# Tray2_BCR.net
KiCad netlist of a schematic drawn in Altium Designer
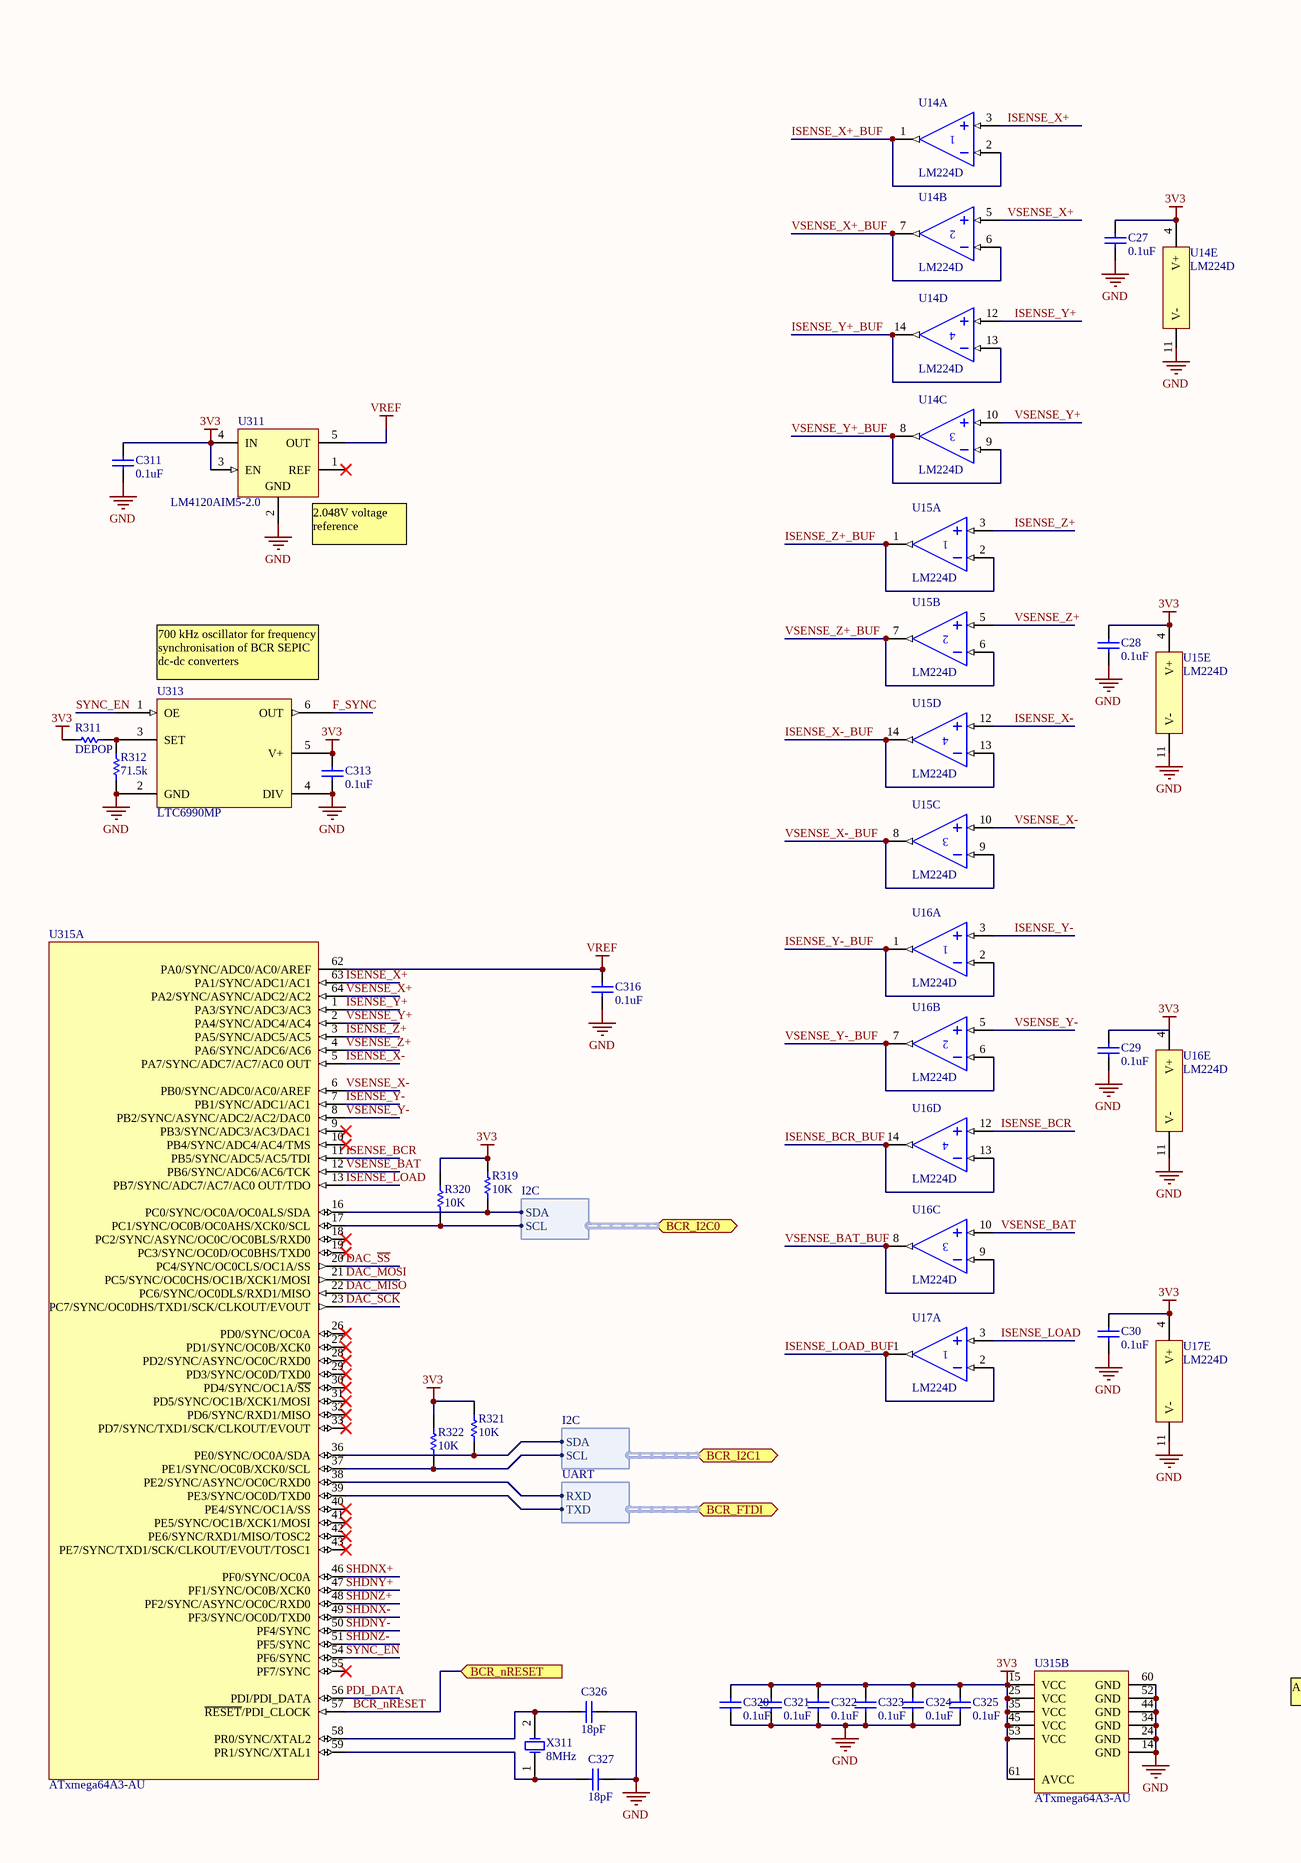
[diagram p0: Tray2_BCR.SchDoc, left]
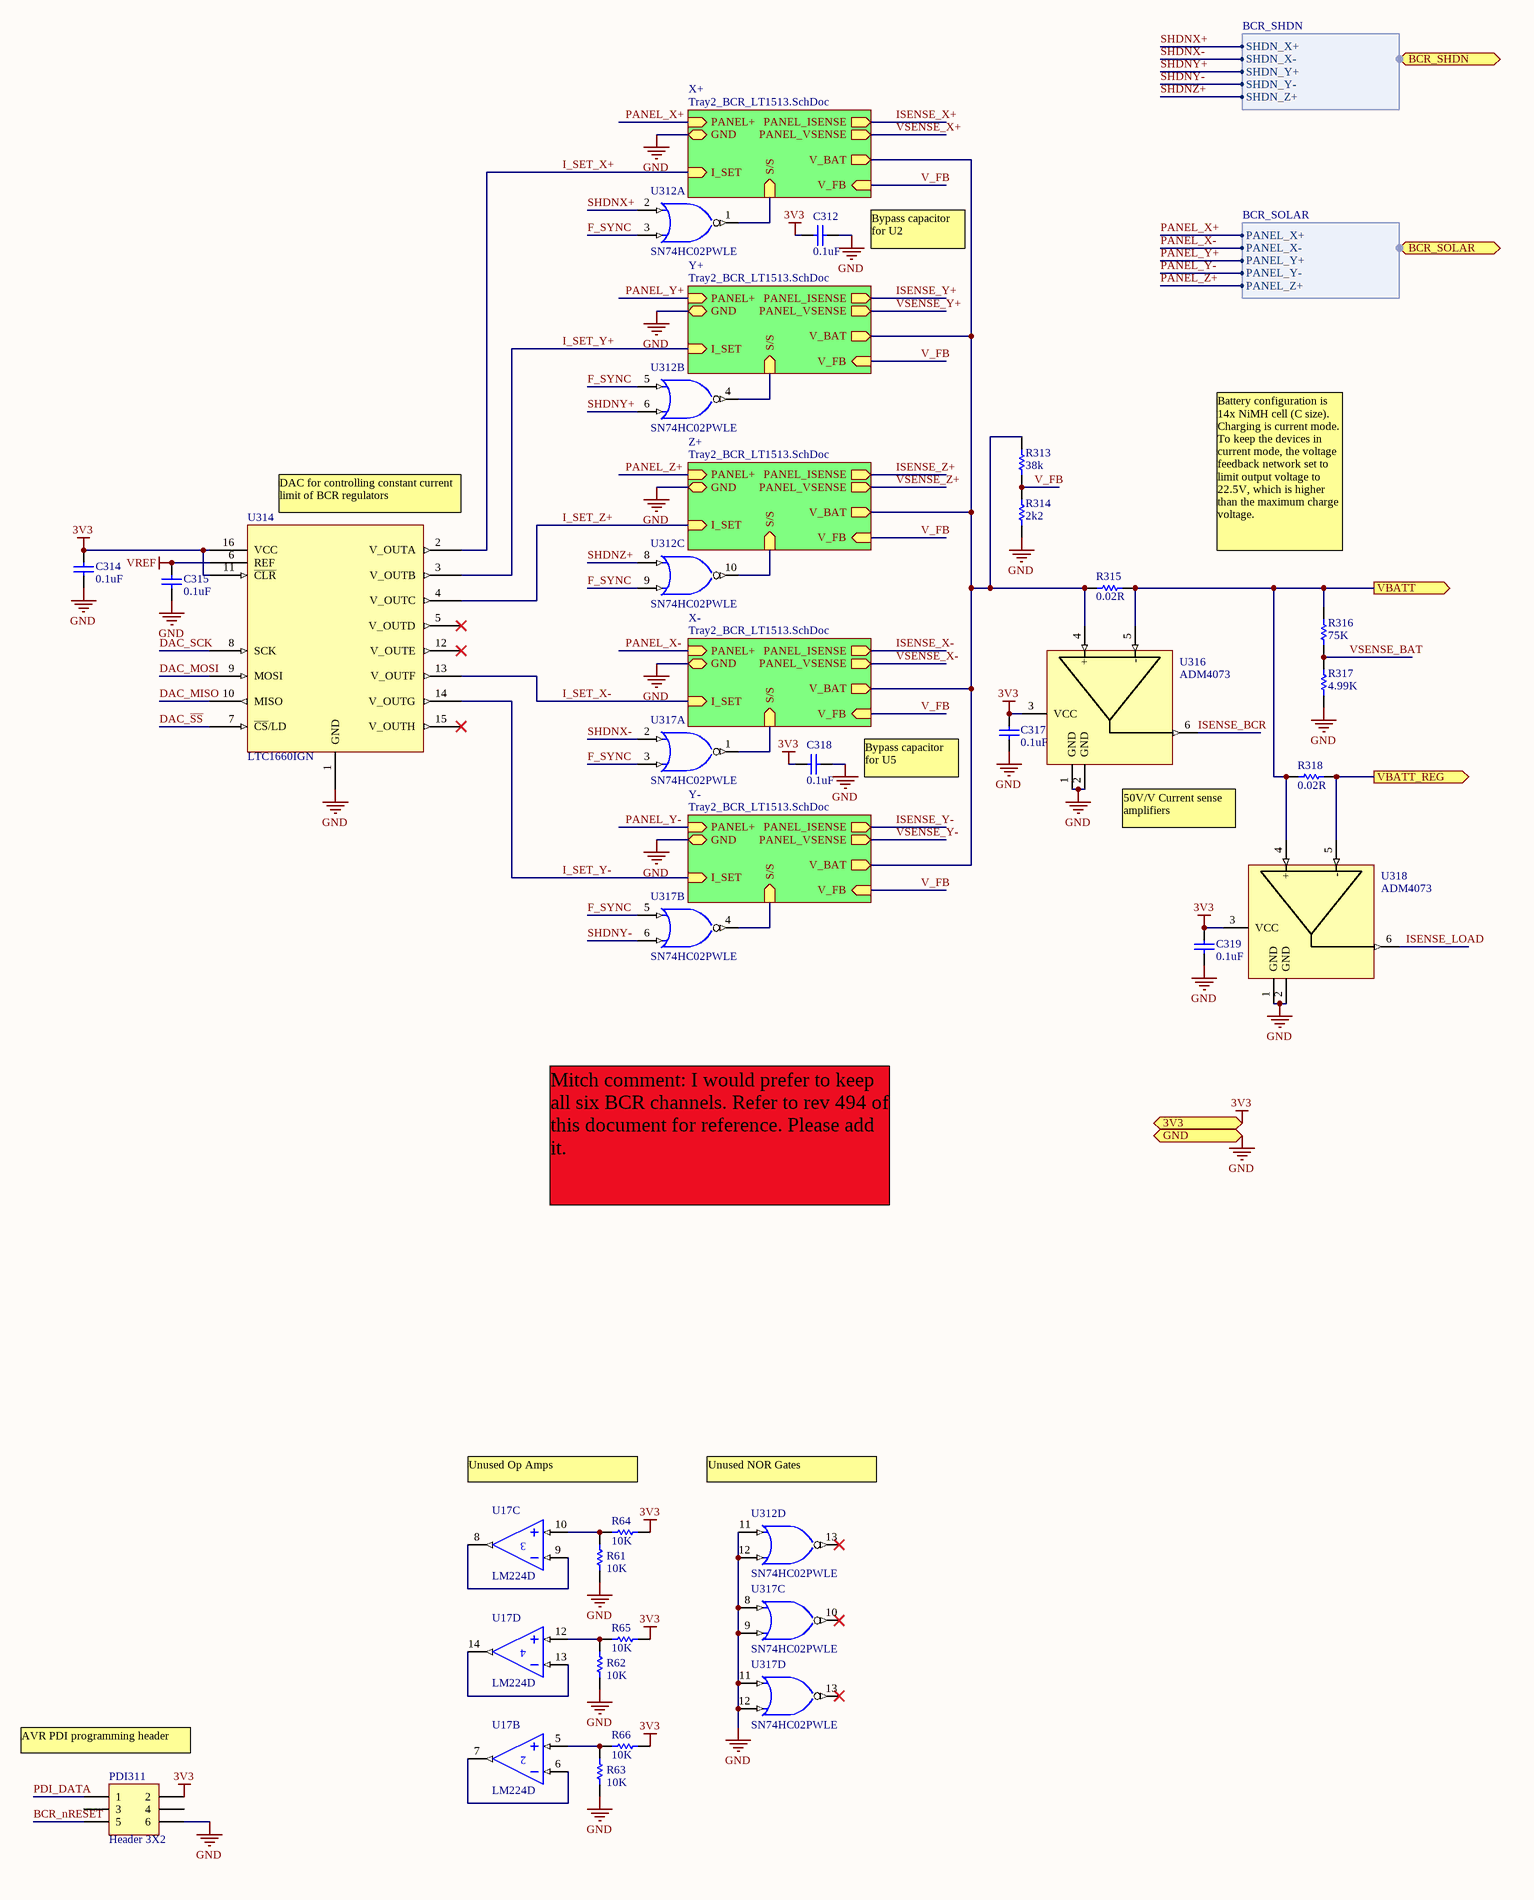
[diagram p1: Tray2_BCR.SchDoc, right]

(export (version "E")
  (design (tool "Eeschema 10.0.6"))
  (components
    (comp (ref "C27")
      (value "0.1uF")
      (footprint "CAPC2012M")
      (description "Capacitor")
      (fields (field (name "Comment") "Cap") (field (name "PUBLISHER") "Altium Limited"))
      (libsource (lib "Miscellaneous Devices") (part "Cap"))
    )
    (comp (ref "C28")
      (value "0.1uF")
      (footprint "CAPC2012M")
      (description "Capacitor")
      (fields (field (name "Comment") "Cap") (field (name "PUBLISHER") "Altium Limited"))
      (libsource (lib "Miscellaneous Devices") (part "Cap"))
    )
    (comp (ref "C29")
      (value "0.1uF")
      (footprint "CAPC2012M")
      (description "Capacitor")
      (fields (field (name "Comment") "Cap") (field (name "PUBLISHER") "Altium Limited"))
      (libsource (lib "Miscellaneous Devices") (part "Cap"))
    )
    (comp (ref "C30")
      (value "0.1uF")
      (footprint "CAPC2012M")
      (description "Capacitor")
      (fields (field (name "Comment") "Cap") (field (name "PUBLISHER") "Altium Limited"))
      (libsource (lib "Miscellaneous Devices") (part "Cap"))
    )
    (comp (ref "C311")
      (value "0.1uF")
      (footprint "CAPC2012M")
      (description "Capacitor")
      (fields (field (name "Comment") "Cap") (field (name "PUBLISHER") "Altium Limited"))
      (libsource (lib "Miscellaneous Devices") (part "Cap"))
    )
    (comp (ref "C312")
      (value "0.1uF")
      (footprint "CAPC2012M")
      (description "Capacitor")
      (fields (field (name "Comment") "Cap") (field (name "PUBLISHER") "Altium Limited"))
      (libsource (lib "Miscellaneous Devices") (part "Cap"))
    )
    (comp (ref "C313")
      (value "0.1uF")
      (footprint "CAPC2012M")
      (description "Capacitor")
      (fields (field (name "Comment") "Cap") (field (name "PUBLISHER") "Altium Limited"))
      (libsource (lib "Miscellaneous Devices") (part "Cap"))
    )
    (comp (ref "C314")
      (value "0.1uF")
      (footprint "CAPC2012M")
      (description "Capacitor")
      (fields (field (name "Comment") "Cap") (field (name "PUBLISHER") "Altium Limited"))
      (libsource (lib "Miscellaneous Devices") (part "Cap"))
    )
    (comp (ref "C315")
      (value "0.1uF")
      (footprint "CAPC2012M")
      (description "Capacitor")
      (fields (field (name "Comment") "Cap") (field (name "PUBLISHER") "Altium Limited"))
      (libsource (lib "Miscellaneous Devices") (part "Cap"))
    )
    (comp (ref "C316")
      (value "0.1uF")
      (footprint "CAPC2012M")
      (description "Capacitor")
      (fields (field (name "Comment") "Cap") (field (name "PUBLISHER") "Altium Limited"))
      (libsource (lib "Miscellaneous Devices") (part "Cap"))
    )
    (comp (ref "C317")
      (value "0.1uF")
      (footprint "CAPC2012M")
      (description "Capacitor")
      (fields (field (name "Comment") "Cap") (field (name "PUBLISHER") "Altium Limited"))
      (libsource (lib "Miscellaneous Devices") (part "Cap"))
    )
    (comp (ref "C318")
      (value "0.1uF")
      (footprint "CAPC2012M")
      (description "Capacitor")
      (fields (field (name "Comment") "Cap") (field (name "PUBLISHER") "Altium Limited"))
      (libsource (lib "Miscellaneous Devices") (part "Cap"))
    )
    (comp (ref "C319")
      (value "0.1uF")
      (footprint "CAPC2012M")
      (description "Capacitor")
      (fields (field (name "Comment") "Cap") (field (name "PUBLISHER") "Altium Limited"))
      (libsource (lib "Miscellaneous Devices") (part "Cap"))
    )
    (comp (ref "C320")
      (value "0.1uF")
      (footprint "CAPC2012M")
      (description "Capacitor")
      (fields (field (name "Comment") "Cap") (field (name "PUBLISHER") "Altium Limited"))
      (libsource (lib "Miscellaneous Devices") (part "Cap"))
    )
    (comp (ref "C321")
      (value "0.1uF")
      (footprint "CAPC2012M")
      (description "Capacitor")
      (fields (field (name "Comment") "Cap") (field (name "PUBLISHER") "Altium Limited"))
      (libsource (lib "Miscellaneous Devices") (part "Cap"))
    )
    (comp (ref "C322")
      (value "0.1uF")
      (footprint "CAPC2012M")
      (description "Capacitor")
      (fields (field (name "Comment") "Cap") (field (name "PUBLISHER") "Altium Limited"))
      (libsource (lib "Miscellaneous Devices") (part "Cap"))
    )
    (comp (ref "C323")
      (value "0.1uF")
      (footprint "CAPC2012M")
      (description "Capacitor")
      (fields (field (name "Comment") "Cap") (field (name "PUBLISHER") "Altium Limited"))
      (libsource (lib "Miscellaneous Devices") (part "Cap"))
    )
    (comp (ref "C324")
      (value "0.1uF")
      (footprint "CAPC2012M")
      (description "Capacitor")
      (fields (field (name "Comment") "Cap") (field (name "PUBLISHER") "Altium Limited"))
      (libsource (lib "Miscellaneous Devices") (part "Cap"))
    )
    (comp (ref "C325")
      (value "0.1uF")
      (footprint "CAPC2012M")
      (description "Capacitor")
      (fields (field (name "Comment") "Cap") (field (name "PUBLISHER") "Altium Limited"))
      (libsource (lib "Miscellaneous Devices") (part "Cap"))
    )
    (comp (ref "C326")
      (value "18pF")
      (footprint "CAPC2012M")
      (description "Capacitor")
      (fields (field (name "Comment") "Cap") (field (name "PUBLISHER") "Altium Limited"))
      (libsource (lib "Miscellaneous Devices") (part "Cap"))
    )
    (comp (ref "C327")
      (value "18pF")
      (footprint "CAPC2012M")
      (description "Capacitor")
      (fields (field (name "Comment") "Cap") (field (name "PUBLISHER") "Altium Limited"))
      (libsource (lib "Miscellaneous Devices") (part "Cap"))
    )
    (comp (ref "PDI311")
      (value "Header 3X2")
      (footprint "HDR2X3")
      (description "Header, 3-Pin, Dual row")
      (fields (field (name "PUBLISHER") "Altium Limited"))
      (libsource (lib "Miscellaneous Connectors") (part "Header 3X2"))
    )
    (comp (ref "R61")
      (value "10K")
      (footprint "RESC2012M")
      (description "Resistor")
      (fields (field (name "Comment") "Res1") (field (name "PUBLISHER") "Altium Limited"))
      (libsource (lib "Miscellaneous Devices") (part "Res1"))
    )
    (comp (ref "R62")
      (value "10K")
      (footprint "RESC2012M")
      (description "Resistor")
      (fields (field (name "Comment") "Res1") (field (name "PUBLISHER") "Altium Limited"))
      (libsource (lib "Miscellaneous Devices") (part "Res1"))
    )
    (comp (ref "R63")
      (value "10K")
      (footprint "RESC2012M")
      (description "Resistor")
      (fields (field (name "Comment") "Res1") (field (name "PUBLISHER") "Altium Limited"))
      (libsource (lib "Miscellaneous Devices") (part "Res1"))
    )
    (comp (ref "R64")
      (value "10K")
      (footprint "RESC2012M")
      (description "Resistor")
      (fields (field (name "Comment") "Res1") (field (name "PUBLISHER") "Altium Limited"))
      (libsource (lib "Miscellaneous Devices") (part "Res1"))
    )
    (comp (ref "R65")
      (value "10K")
      (footprint "RESC2012M")
      (description "Resistor")
      (fields (field (name "Comment") "Res1") (field (name "PUBLISHER") "Altium Limited"))
      (libsource (lib "Miscellaneous Devices") (part "Res1"))
    )
    (comp (ref "R66")
      (value "10K")
      (footprint "RESC2012M")
      (description "Resistor")
      (fields (field (name "Comment") "Res1") (field (name "PUBLISHER") "Altium Limited"))
      (libsource (lib "Miscellaneous Devices") (part "Res1"))
    )
    (comp (ref "R311")
      (value "DEPOP")
      (footprint "RESC2012M")
      (description "Resistor")
      (fields (field (name "Comment") "Res1") (field (name "PUBLISHER") "Altium Limited"))
      (libsource (lib "Miscellaneous Devices") (part "Res1"))
    )
    (comp (ref "R312")
      (value "71.5k")
      (footprint "RESC2012M")
      (description "Resistor")
      (fields (field (name "Comment") "Res1") (field (name "PUBLISHER") "Altium Limited"))
      (libsource (lib "Miscellaneous Devices") (part "Res1"))
    )
    (comp (ref "R313")
      (value "38k")
      (footprint "RESC2012M")
      (description "Resistor")
      (fields (field (name "Comment") "Res1") (field (name "PUBLISHER") "Altium Limited"))
      (libsource (lib "Miscellaneous Devices") (part "Res1"))
    )
    (comp (ref "R314")
      (value "2k2")
      (footprint "RESC2012M")
      (description "Resistor")
      (fields (field (name "Comment") "Res1") (field (name "PUBLISHER") "Altium Limited"))
      (libsource (lib "Miscellaneous Devices") (part "Res1"))
    )
    (comp (ref "R315")
      (value "0.02R")
      (footprint "RESC2012M")
      (description "Resistor")
      (fields (field (name "Comment") "0805 Resistor") (field (name "PUBLISHER") "Altium Limited"))
      (libsource (lib "Miscellaneous Devices") (part "Res1"))
    )
    (comp (ref "R316")
      (value "75K")
      (footprint "RESC2012M")
      (description "Resistor")
      (fields (field (name "Comment") "Res1") (field (name "PUBLISHER") "Altium Limited"))
      (libsource (lib "Miscellaneous Devices") (part "Res1"))
    )
    (comp (ref "R317")
      (value "4.99K")
      (footprint "RESC2012M")
      (description "Resistor")
      (fields (field (name "Comment") "Res1") (field (name "PUBLISHER") "Altium Limited"))
      (libsource (lib "Miscellaneous Devices") (part "Res1"))
    )
    (comp (ref "R318")
      (value "0.02R")
      (footprint "RESC2012M")
      (description "Resistor")
      (fields (field (name "Comment") "0805 Resistor") (field (name "PUBLISHER") "Altium Limited"))
      (libsource (lib "Miscellaneous Devices") (part "Res1"))
    )
    (comp (ref "R319")
      (value "10K")
      (footprint "RESC2012M")
      (description "Resistor")
      (fields (field (name "Comment") "Res1") (field (name "PUBLISHER") "Altium Limited"))
      (libsource (lib "Miscellaneous Devices") (part "Res1"))
    )
    (comp (ref "R320")
      (value "10K")
      (footprint "RESC2012M")
      (description "Resistor")
      (fields (field (name "Comment") "Res1") (field (name "PUBLISHER") "Altium Limited"))
      (libsource (lib "Miscellaneous Devices") (part "Res1"))
    )
    (comp (ref "R321")
      (value "10K")
      (footprint "RESC2012M")
      (description "Resistor")
      (fields (field (name "Comment") "Res1") (field (name "PUBLISHER") "Altium Limited"))
      (libsource (lib "Miscellaneous Devices") (part "Res1"))
    )
    (comp (ref "R322")
      (value "10K")
      (footprint "RESC2012M")
      (description "Resistor")
      (fields (field (name "Comment") "Res1") (field (name "PUBLISHER") "Altium Limited"))
      (libsource (lib "Miscellaneous Devices") (part "Res1"))
    )
    (comp (ref "U14")
      (value "LM224D")
      (footprint "D014_N")
      (description "Quadruple Operational Amplifier")
      (fields (field (name "PUBLISHER") "Altium Limited"))
      (libsource (lib "") (part "LM224D_1"))
    )
    (comp (ref "U15")
      (value "LM224D")
      (footprint "D014_N")
      (description "Quadruple Operational Amplifier")
      (fields (field (name "PUBLISHER") "Altium Limited"))
      (libsource (lib "Tray2") (part "LM224D"))
    )
    (comp (ref "U16")
      (value "LM224D")
      (footprint "D014_N")
      (description "Quadruple Operational Amplifier")
      (fields (field (name "PUBLISHER") "Altium Limited"))
      (libsource (lib "") (part "LM224D_1"))
    )
    (comp (ref "U17")
      (value "LM224D")
      (footprint "D014_N")
      (description "Quadruple Operational Amplifier")
      (fields (field (name "PUBLISHER") "Altium Limited"))
      (libsource (lib "") (part "LM224D_1"))
    )
    (comp (ref "U311")
      (value "LM4120AIM5-2.0")
      (footprint "MF05A_N")
      (description "Precision Micropower Low Dropout Voltage Reference")
      (fields
        (field (name "MANUFACTURER") "National Semiconductor")
        (field (name "DIGIKEYPARTNUMBER") "LM4120AIM5-2.0CT-ND")
        (field (name "PUBLISHER") "Altium Limited")
      )
      (libsource (lib "NSC Voltage Reference") (part "LM4120AIM5-2.0"))
    )
    (comp (ref "U312")
      (value "SN74HC02PWLE")
      (footprint "TSOP65P640-14AN")
      (description "Quadruple 2-Input Positive-NOR Gate")
      (fields (field (name "PUBLISHER") "Altium Limited"))
      (libsource (lib "TI Logic Gate 2") (part "SN74HC02PWLE"))
    )
    (comp (ref "U313") (value "LTC6990MP") (footprint "SOT26A-6L") (libsource (lib "BCR") (part "LTC6990MP")))
    (comp (ref "U314")
      (value "LTC1660IGN")
      (footprint "SOP635P600-16N")
      (libsource (lib "BCR") (part "LTC1660IGN"))
    )
    (comp (ref "U315")
      (value "ATxmega64A3-AU")
      (footprint "64A_N")
      (libsource (lib "Atmel Microcontroller AVR XMEGA") (part "ATxmega64A3-AU"))
    )
    (comp (ref "U316")
      (value "ADM4073")
      (footprint "SOT26A-6N")
      (description "Current Sense Amplifer")
      (libsource (lib "Schlib1") (part "ADM4073"))
    )
    (comp (ref "U317")
      (value "SN74HC02PWLE")
      (footprint "TSOP65P640-14AN")
      (description "Quadruple 2-Input Positive-NOR Gate")
      (fields (field (name "PUBLISHER") "Altium Limited"))
      (libsource (lib "") (part "SN74HC02PWLE_1"))
    )
    (comp (ref "U318")
      (value "ADM4073")
      (footprint "SOT26A-6N")
      (description "Current Sense Amplifer")
      (libsource (lib "Schlib1") (part "ADM4073"))
    )
    (comp (ref "X311")
      (value "8MHz")
      (footprint "HC49 - No border")
      (description "Crystal Oscillator")
      (fields (field (name "PUBLISHER") "Altium Limited"))
      (libsource (lib "Miscellaneous Devices") (part "XTAL"))
    )
  )
  (nets
    (net (code "5") (name "/BCR_nRESET") (class "Default")
      (node (ref "PDI311") (pin "5") (pinfunction "5_5") (pintype "passive"))
      (node (ref "U315") (pin "57") (pinfunction "~{RESET}/PDI_CLOCK_57") (pintype "input"))
    )
    (net (code "6") (name "/DAC_MISO") (class "Default")
      (node (ref "U314") (pin "10") (pinfunction "MISO_10") (pintype "output"))
      (node (ref "U315") (pin "22") (pinfunction "PC6/SYNC/OC0DLS/RXD1/MISO_22") (pintype "input"))
    )
    (net (code "7") (name "/DAC_MOSI") (class "Default")
      (node (ref "U314") (pin "9") (pinfunction "MOSI_9") (pintype "input"))
      (node (ref "U315") (pin "21") (pinfunction "PC5/SYNC/OC0CHS/OC1B/XCK1/MOSI_21") (pintype "output"))
    )
    (net (code "8") (name "/DAC_SCK") (class "Default")
      (node (ref "U314") (pin "8") (pinfunction "SCK_8") (pintype "input"))
      (node (ref "U315") (pin "23") (pinfunction "PC7/SYNC/OC0DHS/TXD1/SCK/CLKOUT/EVOUT_23") (pintype "output"))
    )
    (net (code "9") (name "/DAC_~{SS}") (class "Default")
      (node (ref "U314") (pin "7") (pinfunction "~{CS}/LD_7") (pintype "input"))
      (node (ref "U315") (pin "20") (pinfunction "PC4/SYNC/OC0CLS/OC1A/SS_20") (pintype "output"))
    )
    (net (code "10") (name "/F_SYNC") (class "Default")
      (node (ref "U312") (pin "3") (pinfunction "B_3") (pintype "input"))
      (node (ref "U312") (pin "5") (pinfunction "A_5") (pintype "input"))
      (node (ref "U312") (pin "9") (pinfunction "B_9") (pintype "input"))
      (node (ref "U313") (pin "6") (pinfunction "OUT_6") (pintype "output"))
      (node (ref "U317") (pin "3") (pinfunction "B_3") (pintype "input"))
      (node (ref "U317") (pin "5") (pinfunction "A_5") (pintype "input"))
    )
    (net (code "11") (name "/ISENSE_BCR") (class "Default")
      (node (ref "U16") (pin "12") (pinfunction "IN+_12") (pintype "input"))
      (node (ref "U315") (pin "11") (pinfunction "PB5/SYNC/ADC5/AC5/TDI_11") (pintype "input"))
      (node (ref "U316") (pin "6") (pintype "output"))
    )
    (net (code "12") (name "/ISENSE_BCR_BUF") (class "Default")
      (node (ref "U16") (pin "13") (pinfunction "IN-_13") (pintype "input"))
      (node (ref "U16") (pin "14") (pinfunction "OUT_14") (pintype "output"))
    )
    (net (code "13") (name "/ISENSE_LOAD") (class "Default")
      (node (ref "U17") (pin "3") (pinfunction "IN+_3") (pintype "input"))
      (node (ref "U315") (pin "13") (pinfunction "PB7/SYNC/ADC7/AC7/AC0_OUT/TDO_13") (pintype "input"))
      (node (ref "U318") (pin "6") (pintype "output"))
    )
    (net (code "14") (name "/ISENSE_LOAD_BUF") (class "Default")
      (node (ref "U17") (pin "1") (pinfunction "OUT_1") (pintype "output"))
      (node (ref "U17") (pin "2") (pinfunction "IN-_2") (pintype "input"))
    )
    (net (code "15") (name "/ISENSE_X+") (class "Default")
      (node (ref "U14") (pin "3") (pinfunction "IN+_3") (pintype "input"))
      (node (ref "U315") (pin "63") (pinfunction "PA1/SYNC/ADC1/AC1_63") (pintype "input"))
    )
    (net (code "16") (name "/ISENSE_X+_BUF") (class "Default")
      (node (ref "U14") (pin "1") (pinfunction "OUT_1") (pintype "output"))
      (node (ref "U14") (pin "2") (pinfunction "IN-_2") (pintype "input"))
    )
    (net (code "17") (name "/ISENSE_X-") (class "Default")
      (node (ref "U15") (pin "12") (pinfunction "IN+_12") (pintype "input"))
      (node (ref "U315") (pin "5") (pinfunction "PA7/SYNC/ADC7/AC7/AC0_OUT_5") (pintype "input"))
    )
    (net (code "18") (name "/ISENSE_X-_BUF") (class "Default")
      (node (ref "U15") (pin "13") (pinfunction "IN-_13") (pintype "input"))
      (node (ref "U15") (pin "14") (pinfunction "OUT_14") (pintype "output"))
    )
    (net (code "19") (name "/ISENSE_Y+") (class "Default")
      (node (ref "U14") (pin "12") (pinfunction "IN+_12") (pintype "input"))
      (node (ref "U315") (pin "1") (pinfunction "PA3/SYNC/ADC3/AC3_1") (pintype "input"))
    )
    (net (code "20") (name "/ISENSE_Y+_BUF") (class "Default")
      (node (ref "U14") (pin "13") (pinfunction "IN-_13") (pintype "input"))
      (node (ref "U14") (pin "14") (pinfunction "OUT_14") (pintype "output"))
    )
    (net (code "21") (name "/ISENSE_Y-") (class "Default")
      (node (ref "U16") (pin "3") (pinfunction "IN+_3") (pintype "input"))
      (node (ref "U315") (pin "7") (pinfunction "PB1/SYNC/ADC1/AC1_7") (pintype "input"))
    )
    (net (code "22") (name "/ISENSE_Y-_BUF") (class "Default")
      (node (ref "U16") (pin "1") (pinfunction "OUT_1") (pintype "output"))
      (node (ref "U16") (pin "2") (pinfunction "IN-_2") (pintype "input"))
    )
    (net (code "23") (name "/ISENSE_Z+") (class "Default")
      (node (ref "U15") (pin "3") (pinfunction "IN+_3") (pintype "input"))
      (node (ref "U315") (pin "3") (pinfunction "PA5/SYNC/ADC5/AC5_3") (pintype "input"))
    )
    (net (code "24") (name "/ISENSE_Z+_BUF") (class "Default")
      (node (ref "U15") (pin "1") (pinfunction "OUT_1") (pintype "output"))
      (node (ref "U15") (pin "2") (pinfunction "IN-_2") (pintype "input"))
    )
    (net (code "25") (name "/I_SET_X+") (class "Default")
      (node (ref "U314") (pin "2") (pinfunction "V_OUTA_2") (pintype "output"))
    )
    (net (code "26") (name "/I_SET_X-") (class "Default")
      (node (ref "U314") (pin "13") (pinfunction "V_OUTF_13") (pintype "output"))
    )
    (net (code "27") (name "/I_SET_Y+") (class "Default")
      (node (ref "U314") (pin "3") (pinfunction "V_OUTB_3") (pintype "output"))
    )
    (net (code "28") (name "/I_SET_Y-") (class "Default")
      (node (ref "U314") (pin "14") (pinfunction "V_OUTG_14") (pintype "output"))
    )
    (net (code "29") (name "/I_SET_Z+") (class "Default")
      (node (ref "U314") (pin "4") (pinfunction "V_OUTC_4") (pintype "output"))
    )
    (net (code "35") (name "/PDI_DATA") (class "Default")
      (node (ref "PDI311") (pin "1") (pinfunction "1_1") (pintype "passive"))
      (node (ref "U315") (pin "56") (pinfunction "PDI/PDI_DATA_56") (pintype "bidirectional"))
    )
    (net (code "36") (name "/RXD") (class "Default")
      (node (ref "U315") (pin "38") (pinfunction "PE2/SYNC/ASYNC/OC0C/RXD0_38") (pintype "bidirectional"))
    )
    (net (code "37") (name "/SHDNX+") (class "Default")
      (node (ref "U312") (pin "2") (pinfunction "A_2") (pintype "input"))
      (node (ref "U315") (pin "46") (pinfunction "PF0/SYNC/OC0A_46") (pintype "bidirectional"))
    )
    (net (code "38") (name "/SHDNX-") (class "Default")
      (node (ref "U315") (pin "49") (pinfunction "PF3/SYNC/OC0D/TXD0_49") (pintype "bidirectional"))
      (node (ref "U317") (pin "2") (pinfunction "A_2") (pintype "input"))
    )
    (net (code "39") (name "/SHDNY+") (class "Default")
      (node (ref "U312") (pin "6") (pinfunction "B_6") (pintype "input"))
      (node (ref "U315") (pin "47") (pinfunction "PF1/SYNC/OC0B/XCK0_47") (pintype "bidirectional"))
    )
    (net (code "40") (name "/SHDNY-") (class "Default")
      (node (ref "U315") (pin "50") (pinfunction "PF4/SYNC_50") (pintype "bidirectional"))
      (node (ref "U317") (pin "6") (pinfunction "B_6") (pintype "input"))
    )
    (net (code "41") (name "/SHDNZ+") (class "Default")
      (node (ref "U312") (pin "8") (pinfunction "A_8") (pintype "input"))
      (node (ref "U315") (pin "48") (pinfunction "PF2/SYNC/ASYNC/OC0C/RXD0_48") (pintype "bidirectional"))
    )
    (net (code "42") (name "/SHDNZ-") (class "Default")
      (node (ref "U315") (pin "51") (pinfunction "PF5/SYNC_51") (pintype "bidirectional"))
    )
    (net (code "43") (name "/SYNC_EN") (class "Default")
      (node (ref "U313") (pin "1") (pinfunction "OE_1") (pintype "input"))
      (node (ref "U315") (pin "54") (pinfunction "PF6/SYNC_54") (pintype "bidirectional"))
    )
    (net (code "44") (name "/S{slash}S") (class "Default")
      (node (ref "U312") (pin "1") (pinfunction "Y_1") (pintype "output"))
    )
    (net (code "45") (name "/S{slash}S_1") (class "Default")
      (node (ref "U312") (pin "4") (pinfunction "Y_4") (pintype "output"))
    )
    (net (code "46") (name "/S{slash}S_2") (class "Default")
      (node (ref "U312") (pin "10") (pinfunction "Y_10") (pintype "output"))
    )
    (net (code "47") (name "/S{slash}S_3") (class "Default")
      (node (ref "U317") (pin "1") (pinfunction "Y_1") (pintype "output"))
    )
    (net (code "48") (name "/S{slash}S_4") (class "Default")
      (node (ref "U317") (pin "4") (pinfunction "Y_4") (pintype "output"))
    )
    (net (code "49") (name "/TXD") (class "Default")
      (node (ref "U315") (pin "39") (pinfunction "PE3/SYNC/OC0D/TXD0_39") (pintype "bidirectional"))
    )
    (net (code "50") (name "/VBATT") (class "Default")
      (node (ref "R315") (pin "2") (pinfunction "2_2") (pintype "passive"))
      (node (ref "R316") (pin "1") (pinfunction "1_1") (pintype "passive"))
      (node (ref "R318") (pin "2") (pinfunction "2_2") (pintype "passive"))
      (node (ref "U316") (pin "5") (pinfunction "-_5") (pintype "input"))
      (node (ref "U318") (pin "4") (pinfunction "+_4") (pintype "input"))
    )
    (net (code "51") (name "/VBATT_REG") (class "Default")
      (node (ref "R318") (pin "1") (pinfunction "1_1") (pintype "passive"))
      (node (ref "U318") (pin "5") (pinfunction "-_5") (pintype "input"))
    )
    (net (code "52") (name "/VSENSE_BAT") (class "Default")
      (node (ref "R316") (pin "2") (pinfunction "2_2") (pintype "passive"))
      (node (ref "R317") (pin "1") (pinfunction "1_1") (pintype "passive"))
      (node (ref "U16") (pin "10") (pinfunction "IN+_10") (pintype "input"))
      (node (ref "U315") (pin "12") (pinfunction "PB6/SYNC/ADC6/AC6/TCK_12") (pintype "input"))
    )
    (net (code "53") (name "/VSENSE_BAT_BUF") (class "Default")
      (node (ref "U16") (pin "8") (pinfunction "OUT_8") (pintype "output"))
      (node (ref "U16") (pin "9") (pinfunction "IN-_9") (pintype "input"))
    )
    (net (code "54") (name "/VSENSE_X+") (class "Default")
      (node (ref "U14") (pin "5") (pinfunction "IN+_5") (pintype "input"))
      (node (ref "U315") (pin "64") (pinfunction "PA2/SYNC/ASYNC/ADC2/AC2_64") (pintype "input"))
    )
    (net (code "55") (name "/VSENSE_X+_BUF") (class "Default")
      (node (ref "U14") (pin "6") (pinfunction "IN-_6") (pintype "input"))
      (node (ref "U14") (pin "7") (pinfunction "OUT_7") (pintype "output"))
    )
    (net (code "56") (name "/VSENSE_X-") (class "Default")
      (node (ref "U15") (pin "10") (pinfunction "IN+_10") (pintype "input"))
      (node (ref "U315") (pin "6") (pinfunction "PB0/SYNC/ADC0/AC0/AREF_6") (pintype "input"))
    )
    (net (code "57") (name "/VSENSE_X-_BUF") (class "Default")
      (node (ref "U15") (pin "8") (pinfunction "OUT_8") (pintype "output"))
      (node (ref "U15") (pin "9") (pinfunction "IN-_9") (pintype "input"))
    )
    (net (code "58") (name "/VSENSE_Y+") (class "Default")
      (node (ref "U14") (pin "10") (pinfunction "IN+_10") (pintype "input"))
      (node (ref "U315") (pin "2") (pinfunction "PA4/SYNC/ADC4/AC4_2") (pintype "input"))
    )
    (net (code "59") (name "/VSENSE_Y+_BUF") (class "Default")
      (node (ref "U14") (pin "8") (pinfunction "OUT_8") (pintype "output"))
      (node (ref "U14") (pin "9") (pinfunction "IN-_9") (pintype "input"))
    )
    (net (code "60") (name "/VSENSE_Y-") (class "Default")
      (node (ref "U16") (pin "5") (pinfunction "IN+_5") (pintype "input"))
      (node (ref "U315") (pin "8") (pinfunction "PB2/SYNC/ASYNC/ADC2/AC2/DAC0_8") (pintype "input"))
    )
    (net (code "61") (name "/VSENSE_Y-_BUF") (class "Default")
      (node (ref "U16") (pin "6") (pinfunction "IN-_6") (pintype "input"))
      (node (ref "U16") (pin "7") (pinfunction "OUT_7") (pintype "output"))
    )
    (net (code "62") (name "/VSENSE_Z+") (class "Default")
      (node (ref "U15") (pin "5") (pinfunction "IN+_5") (pintype "input"))
      (node (ref "U315") (pin "4") (pinfunction "PA6/SYNC/ADC6/AC6_4") (pintype "input"))
    )
    (net (code "63") (name "/VSENSE_Z+_BUF") (class "Default")
      (node (ref "U15") (pin "6") (pinfunction "IN-_6") (pintype "input"))
      (node (ref "U15") (pin "7") (pinfunction "OUT_7") (pintype "output"))
    )
    (net (code "64") (name "/V_BAT") (class "Default")
      (node (ref "R313") (pin "2") (pinfunction "2_2") (pintype "passive"))
      (node (ref "R315") (pin "1") (pinfunction "1_1") (pintype "passive"))
      (node (ref "U316") (pin "4") (pinfunction "+_4") (pintype "input"))
    )
    (net (code "65") (name "/V_FB") (class "Default")
      (node (ref "R313") (pin "1") (pinfunction "1_1") (pintype "passive"))
      (node (ref "R314") (pin "2") (pinfunction "2_2") (pintype "passive"))
    )
    (net (code "70") (name "3V3") (class "Default")
      (node (ref "C27") (pin "1") (pinfunction "1_1") (pintype "passive"))
      (node (ref "C28") (pin "1") (pinfunction "1_1") (pintype "passive"))
      (node (ref "C29") (pin "1") (pinfunction "1_1") (pintype "passive"))
      (node (ref "C30") (pin "1") (pinfunction "1_1") (pintype "passive"))
      (node (ref "C311") (pin "2") (pinfunction "2_2") (pintype "passive"))
      (node (ref "C312") (pin "2") (pinfunction "2_2") (pintype "passive"))
      (node (ref "C313") (pin "1") (pinfunction "1_1") (pintype "passive"))
      (node (ref "C314") (pin "2") (pinfunction "2_2") (pintype "passive"))
      (node (ref "C317") (pin "1") (pinfunction "1_1") (pintype "passive"))
      (node (ref "C318") (pin "2") (pinfunction "2_2") (pintype "passive"))
      (node (ref "C319") (pin "1") (pinfunction "1_1") (pintype "passive"))
      (node (ref "C320") (pin "2") (pinfunction "2_2") (pintype "passive"))
      (node (ref "C321") (pin "2") (pinfunction "2_2") (pintype "passive"))
      (node (ref "C322") (pin "2") (pinfunction "2_2") (pintype "passive"))
      (node (ref "C323") (pin "2") (pinfunction "2_2") (pintype "passive"))
      (node (ref "C324") (pin "2") (pinfunction "2_2") (pintype "passive"))
      (node (ref "C325") (pin "2") (pinfunction "2_2") (pintype "passive"))
      (node (ref "PDI311") (pin "2") (pinfunction "2_2") (pintype "passive"))
      (node (ref "R311") (pin "1") (pinfunction "1_1") (pintype "passive"))
      (node (ref "R319") (pin "1") (pinfunction "1_1") (pintype "passive"))
      (node (ref "R320") (pin "1") (pinfunction "1_1") (pintype "passive"))
      (node (ref "R321") (pin "1") (pinfunction "1_1") (pintype "passive"))
      (node (ref "R322") (pin "1") (pinfunction "1_1") (pintype "passive"))
      (node (ref "R64") (pin "2") (pinfunction "2_2") (pintype "passive"))
      (node (ref "R65") (pin "2") (pinfunction "2_2") (pintype "passive"))
      (node (ref "R66") (pin "2") (pinfunction "2_2") (pintype "passive"))
      (node (ref "U14") (pin "4") (pinfunction "V+_4") (pintype "power_in"))
      (node (ref "U15") (pin "4") (pinfunction "V+_4") (pintype "power_in"))
      (node (ref "U17") (pin "4") (pinfunction "V+_4") (pintype "power_in"))
      (node (ref "U311") (pin "3") (pinfunction "EN_3") (pintype "input"))
      (node (ref "U311") (pin "4") (pinfunction "IN_4") (pintype "power_in"))
      (node (ref "U313") (pin "5") (pinfunction "V+_5") (pintype "passive"))
      (node (ref "U314") (pin "11") (pinfunction "~{CLR}_11") (pintype "input"))
      (node (ref "U314") (pin "16") (pinfunction "VCC_16") (pintype "passive"))
      (node (ref "U315") (pin "15") (pinfunction "VCC_15") (pintype "power_in"))
      (node (ref "U315") (pin "25") (pinfunction "VCC_25") (pintype "power_in"))
      (node (ref "U315") (pin "35") (pinfunction "VCC_35") (pintype "power_in"))
      (node (ref "U315") (pin "45") (pinfunction "VCC_45") (pintype "power_in"))
      (node (ref "U315") (pin "53") (pinfunction "VCC_53") (pintype "power_in"))
      (node (ref "U315") (pin "61") (pinfunction "AVCC_61") (pintype "power_in"))
      (node (ref "U316") (pin "3") (pinfunction "VCC_3") (pintype "passive"))
      (node (ref "U318") (pin "3") (pinfunction "VCC_3") (pintype "passive"))
    )
    (net (code "71") (name "GND") (class "Default")
      (node (ref "C27") (pin "2") (pinfunction "2_2") (pintype "passive"))
      (node (ref "C28") (pin "2") (pinfunction "2_2") (pintype "passive"))
      (node (ref "C29") (pin "2") (pinfunction "2_2") (pintype "passive"))
      (node (ref "C30") (pin "2") (pinfunction "2_2") (pintype "passive"))
      (node (ref "C311") (pin "1") (pinfunction "1_1") (pintype "passive"))
      (node (ref "C312") (pin "1") (pinfunction "1_1") (pintype "passive"))
      (node (ref "C313") (pin "2") (pinfunction "2_2") (pintype "passive"))
      (node (ref "C314") (pin "1") (pinfunction "1_1") (pintype "passive"))
      (node (ref "C315") (pin "1") (pinfunction "1_1") (pintype "passive"))
      (node (ref "C316") (pin "1") (pinfunction "1_1") (pintype "passive"))
      (node (ref "C317") (pin "2") (pinfunction "2_2") (pintype "passive"))
      (node (ref "C318") (pin "1") (pinfunction "1_1") (pintype "passive"))
      (node (ref "C319") (pin "2") (pinfunction "2_2") (pintype "passive"))
      (node (ref "C320") (pin "1") (pinfunction "1_1") (pintype "passive"))
      (node (ref "C321") (pin "1") (pinfunction "1_1") (pintype "passive"))
      (node (ref "C322") (pin "1") (pinfunction "1_1") (pintype "passive"))
      (node (ref "C323") (pin "1") (pinfunction "1_1") (pintype "passive"))
      (node (ref "C324") (pin "1") (pinfunction "1_1") (pintype "passive"))
      (node (ref "C325") (pin "1") (pinfunction "1_1") (pintype "passive"))
      (node (ref "C326") (pin "2") (pinfunction "2_2") (pintype "passive"))
      (node (ref "C327") (pin "1") (pinfunction "1_1") (pintype "passive"))
      (node (ref "PDI311") (pin "6") (pinfunction "6_6") (pintype "passive"))
      (node (ref "R312") (pin "1") (pinfunction "1_1") (pintype "passive"))
      (node (ref "R314") (pin "1") (pinfunction "1_1") (pintype "passive"))
      (node (ref "R317") (pin "2") (pinfunction "2_2") (pintype "passive"))
      (node (ref "R61") (pin "2") (pinfunction "2_2") (pintype "passive"))
      (node (ref "R62") (pin "2") (pinfunction "2_2") (pintype "passive"))
      (node (ref "R63") (pin "2") (pinfunction "2_2") (pintype "passive"))
      (node (ref "U16") (pin "11") (pinfunction "V-_11") (pintype "power_in"))
      (node (ref "U311") (pin "2") (pinfunction "GND_2") (pintype "power_in"))
      (node (ref "U312") (pin "11") (pinfunction "A_11") (pintype "input"))
      (node (ref "U312") (pin "12") (pinfunction "B_12") (pintype "input"))
      (node (ref "U312") (pin "7") (pinfunction "GND_7") (pintype "power_in"))
      (node (ref "U313") (pin "2") (pinfunction "GND_2") (pintype "passive"))
      (node (ref "U313") (pin "4") (pinfunction "DIV_4") (pintype "passive"))
      (node (ref "U314") (pin "1") (pinfunction "GND_1") (pintype "passive"))
      (node (ref "U315") (pin "14") (pinfunction "GND_14") (pintype "power_in"))
      (node (ref "U315") (pin "24") (pinfunction "GND_24") (pintype "power_in"))
      (node (ref "U315") (pin "34") (pinfunction "GND_34") (pintype "power_in"))
      (node (ref "U315") (pin "44") (pinfunction "GND_44") (pintype "power_in"))
      (node (ref "U315") (pin "52") (pinfunction "GND_52") (pintype "power_in"))
      (node (ref "U315") (pin "60") (pinfunction "GND_60") (pintype "power_in"))
      (node (ref "U316") (pin "1") (pinfunction "GND_1") (pintype "passive"))
      (node (ref "U316") (pin "2") (pinfunction "GND_2") (pintype "passive"))
      (node (ref "U317") (pin "11") (pinfunction "A_11") (pintype "input"))
      (node (ref "U317") (pin "12") (pinfunction "B_12") (pintype "input"))
      (node (ref "U317") (pin "7") (pinfunction "GND_7") (pintype "power_in"))
      (node (ref "U317") (pin "8") (pinfunction "A_8") (pintype "input"))
      (node (ref "U317") (pin "9") (pinfunction "B_9") (pintype "input"))
      (node (ref "U318") (pin "1") (pinfunction "GND_1") (pintype "passive"))
      (node (ref "U318") (pin "2") (pinfunction "GND_2") (pintype "passive"))
    )
    (net (code "72") (name "Net-(U17B-IN+)") (class "Default")
      (node (ref "R63") (pin "1") (pinfunction "1_1") (pintype "passive"))
      (node (ref "R66") (pin "1") (pinfunction "1_1") (pintype "passive"))
      (node (ref "U17") (pin "5") (pinfunction "IN+_5") (pintype "input"))
    )
    (net (code "73") (name "Net-(U17B-IN-)") (class "Default")
      (node (ref "U17") (pin "6") (pinfunction "IN-_6") (pintype "input"))
      (node (ref "U17") (pin "7") (pinfunction "OUT_7") (pintype "output"))
    )
    (net (code "74") (name "Net-(U17C-IN+)") (class "Default")
      (node (ref "R61") (pin "1") (pinfunction "1_1") (pintype "passive"))
      (node (ref "R64") (pin "1") (pinfunction "1_1") (pintype "passive"))
      (node (ref "U17") (pin "10") (pinfunction "IN+_10") (pintype "input"))
    )
    (net (code "75") (name "Net-(U17C-IN-)") (class "Default")
      (node (ref "U17") (pin "8") (pinfunction "OUT_8") (pintype "output"))
      (node (ref "U17") (pin "9") (pinfunction "IN-_9") (pintype "input"))
    )
    (net (code "76") (name "Net-(U17D-IN+)") (class "Default")
      (node (ref "R62") (pin "1") (pinfunction "1_1") (pintype "passive"))
      (node (ref "R65") (pin "1") (pinfunction "1_1") (pintype "passive"))
      (node (ref "U17") (pin "12") (pinfunction "IN+_12") (pintype "input"))
    )
    (net (code "77") (name "Net-(U17D-IN-)") (class "Default")
      (node (ref "U17") (pin "13") (pinfunction "IN-_13") (pintype "input"))
      (node (ref "U17") (pin "14") (pinfunction "OUT_14") (pintype "output"))
    )
    (net (code "78") (name "Net-(U313-SET)") (class "Default")
      (node (ref "R311") (pin "2") (pinfunction "2_2") (pintype "passive"))
      (node (ref "R312") (pin "2") (pinfunction "2_2") (pintype "passive"))
      (node (ref "U313") (pin "3") (pinfunction "SET_3") (pintype "passive"))
    )
    (net (code "79") (name "Net-(U315A-PC0{slash}SYNC{slash}OC0A{slash}OC0ALS{slash}SDA)") (class "Default")
      (node (ref "R319") (pin "2") (pinfunction "2_2") (pintype "passive"))
      (node (ref "U315") (pin "16") (pinfunction "PC0/SYNC/OC0A/OC0ALS/SDA_16") (pintype "bidirectional"))
    )
    (net (code "80") (name "Net-(U315A-PC1{slash}SYNC{slash}OC0B{slash}OC0AHS{slash}XCK0{slash}SCL)") (class "Default")
      (node (ref "R320") (pin "2") (pinfunction "2_2") (pintype "passive"))
      (node (ref "U315") (pin "17") (pinfunction "PC1/SYNC/OC0B/OC0AHS/XCK0/SCL_17") (pintype "bidirectional"))
    )
    (net (code "81") (name "Net-(U315A-PE0{slash}SYNC{slash}OC0A{slash}SDA)") (class "Default")
      (node (ref "R321") (pin "2") (pinfunction "2_2") (pintype "passive"))
      (node (ref "U315") (pin "36") (pinfunction "PE0/SYNC/OC0A/SDA_36") (pintype "bidirectional"))
    )
    (net (code "82") (name "Net-(U315A-PE1{slash}SYNC{slash}OC0B{slash}XCK0{slash}SCL)") (class "Default")
      (node (ref "R322") (pin "2") (pinfunction "2_2") (pintype "passive"))
      (node (ref "U315") (pin "37") (pinfunction "PE1/SYNC/OC0B/XCK0/SCL_37") (pintype "bidirectional"))
    )
    (net (code "83") (name "Net-(U315A-PR0{slash}SYNC{slash}XTAL2)") (class "Default")
      (node (ref "C326") (pin "1") (pinfunction "1_1") (pintype "passive"))
      (node (ref "U315") (pin "58") (pinfunction "PR0/SYNC/XTAL2_58") (pintype "bidirectional"))
      (node (ref "X311") (pin "2") (pinfunction "OSC2_2") (pintype "passive"))
    )
    (net (code "84") (name "Net-(U315A-PR1{slash}SYNC{slash}XTAL1)") (class "Default")
      (node (ref "C327") (pin "2") (pinfunction "2_2") (pintype "passive"))
      (node (ref "U315") (pin "59") (pinfunction "PR1/SYNC/XTAL1_59") (pintype "bidirectional"))
      (node (ref "X311") (pin "1") (pinfunction "OSC1_1") (pintype "passive"))
    )
    (net (code "85") (name "VCC") (class "Default")
      (node (ref "U312") (pin "14") (pinfunction "VCC_14") (pintype "power_in"))
      (node (ref "U317") (pin "14") (pinfunction "VCC_14") (pintype "power_in"))
    )
    (net (code "86") (name "VREF") (class "Default")
      (node (ref "C315") (pin "2") (pinfunction "2_2") (pintype "passive"))
      (node (ref "C316") (pin "2") (pinfunction "2_2") (pintype "passive"))
      (node (ref "U311") (pin "5") (pinfunction "OUT_5") (pintype "power_in"))
      (node (ref "U314") (pin "6") (pinfunction "REF_6") (pintype "passive"))
      (node (ref "U315") (pin "62") (pinfunction "PA0/SYNC/ADC0/AC0/AREF_62") (pintype "passive"))
    )
    (net (code "87") (name "unconnected-(PDI311-Pad3)") (class "Default")
      (node (ref "PDI311") (pin "3") (pinfunction "3_3") (pintype "passive"))
    )
    (net (code "88") (name "unconnected-(PDI311-Pad4)") (class "Default")
      (node (ref "PDI311") (pin "4") (pinfunction "4_4") (pintype "passive"))
    )
    (net (code "89") (name "unconnected-(U14E-V--Pad11)") (class "Default")
      (node (ref "U14") (pin "11") (pinfunction "V-_11") (pintype "power_in"))
    )
    (net (code "90") (name "unconnected-(U15E-V--Pad11)") (class "Default")
      (node (ref "U15") (pin "11") (pinfunction "V-_11") (pintype "power_in"))
    )
    (net (code "91") (name "unconnected-(U16E-V+-Pad4)") (class "Default")
      (node (ref "U16") (pin "4") (pinfunction "V+_4") (pintype "power_in"))
    )
    (net (code "92") (name "unconnected-(U17E-V--Pad11)") (class "Default")
      (node (ref "U17") (pin "11") (pinfunction "V-_11") (pintype "power_in"))
    )
    (net (code "93") (name "unconnected-(U311-REF-Pad1)") (class "Default")
      (node (ref "U311") (pin "1") (pinfunction "REF_1") (pintype "passive+no_connect"))
    )
    (net (code "94") (name "unconnected-(U312D-Y-Pad13)") (class "Default")
      (node (ref "U312") (pin "13") (pinfunction "Y_13") (pintype "output+no_connect"))
    )
    (net (code "95") (name "unconnected-(U314-V_OUTD-Pad5)") (class "Default")
      (node (ref "U314") (pin "5") (pinfunction "V_OUTD_5") (pintype "output+no_connect"))
    )
    (net (code "96") (name "unconnected-(U314-V_OUTE-Pad12)") (class "Default")
      (node (ref "U314") (pin "12") (pinfunction "V_OUTE_12") (pintype "output+no_connect"))
    )
    (net (code "97") (name "unconnected-(U314-V_OUTH-Pad15)") (class "Default")
      (node (ref "U314") (pin "15") (pinfunction "V_OUTH_15") (pintype "output+no_connect"))
    )
    (net (code "98") (name "unconnected-(U315A-PB3{slash}SYNC{slash}ADC3{slash}AC3{slash}DAC1-Pad9)") (class "Default")
      (node (ref "U315") (pin "9") (pinfunction "PB3/SYNC/ADC3/AC3/DAC1_9") (pintype "input+no_connect"))
    )
    (net (code "99") (name "unconnected-(U315A-PB4{slash}SYNC{slash}ADC4{slash}AC4{slash}TMS-Pad10)") (class "Default")
      (node (ref "U315") (pin "10") (pinfunction "PB4/SYNC/ADC4/AC4/TMS_10") (pintype "input+no_connect"))
    )
    (net (code "100") (name "unconnected-(U315A-PC2{slash}SYNC{slash}ASYNC{slash}OC0C{slash}OC0BLS{slash}RXD0-Pad18)") (class "Default")
      (node (ref "U315") (pin "18") (pinfunction "PC2/SYNC/ASYNC/OC0C/OC0BLS/RXD0_18") (pintype "bidirectional+no_connect"))
    )
    (net (code "101") (name "unconnected-(U315A-PC3{slash}SYNC{slash}OC0D{slash}OC0BHS{slash}TXD0-Pad19)") (class "Default")
      (node (ref "U315") (pin "19") (pinfunction "PC3/SYNC/OC0D/OC0BHS/TXD0_19") (pintype "bidirectional+no_connect"))
    )
    (net (code "102") (name "unconnected-(U315A-PD0{slash}SYNC{slash}OC0A-Pad26)") (class "Default")
      (node (ref "U315") (pin "26") (pinfunction "PD0/SYNC/OC0A_26") (pintype "bidirectional+no_connect"))
    )
    (net (code "103") (name "unconnected-(U315A-PD1{slash}SYNC{slash}OC0B{slash}XCK0-Pad27)") (class "Default")
      (node (ref "U315") (pin "27") (pinfunction "PD1/SYNC/OC0B/XCK0_27") (pintype "bidirectional+no_connect"))
    )
    (net (code "104") (name "unconnected-(U315A-PD2{slash}SYNC{slash}ASYNC{slash}OC0C{slash}RXD0-Pad28)") (class "Default")
      (node (ref "U315") (pin "28") (pinfunction "PD2/SYNC/ASYNC/OC0C/RXD0_28") (pintype "bidirectional+no_connect"))
    )
    (net (code "105") (name "unconnected-(U315A-PD3{slash}SYNC{slash}OC0D{slash}TXD0-Pad29)") (class "Default")
      (node (ref "U315") (pin "29") (pinfunction "PD3/SYNC/OC0D/TXD0_29") (pintype "bidirectional+no_connect"))
    )
    (net (code "106") (name "unconnected-(U315A-PD4{slash}SYNC{slash}OC1A{slash}~{SS}-Pad30)") (class "Default")
      (node (ref "U315") (pin "30") (pinfunction "PD4/SYNC/OC1A/~{SS}_30") (pintype "bidirectional+no_connect"))
    )
    (net (code "107") (name "unconnected-(U315A-PD5{slash}SYNC{slash}OC1B{slash}XCK1{slash}MOSI-Pad31)") (class "Default")
      (node (ref "U315") (pin "31") (pinfunction "PD5/SYNC/OC1B/XCK1/MOSI_31") (pintype "bidirectional+no_connect"))
    )
    (net (code "108") (name "unconnected-(U315A-PD6{slash}SYNC{slash}RXD1{slash}MISO-Pad32)") (class "Default")
      (node (ref "U315") (pin "32") (pinfunction "PD6/SYNC/RXD1/MISO_32") (pintype "bidirectional+no_connect"))
    )
    (net (code "109") (name "unconnected-(U315A-PD7{slash}SYNC{slash}TXD1{slash}SCK{slash}CLKOUT{slash}EVOUT-Pad33)") (class "Default")
      (node (ref "U315") (pin "33") (pinfunction "PD7/SYNC/TXD1/SCK/CLKOUT/EVOUT_33") (pintype "bidirectional+no_connect"))
    )
    (net (code "110") (name "unconnected-(U315A-PE4{slash}SYNC{slash}OC1A{slash}SS-Pad40)") (class "Default")
      (node (ref "U315") (pin "40") (pinfunction "PE4/SYNC/OC1A/SS_40") (pintype "bidirectional+no_connect"))
    )
    (net (code "111") (name "unconnected-(U315A-PE5{slash}SYNC{slash}OC1B{slash}XCK1{slash}MOSI-Pad41)") (class "Default")
      (node (ref "U315") (pin "41") (pinfunction "PE5/SYNC/OC1B/XCK1/MOSI_41") (pintype "bidirectional+no_connect"))
    )
    (net (code "112") (name "unconnected-(U315A-PE6{slash}SYNC{slash}RXD1{slash}MISO{slash}TOSC2-Pad42)") (class "Default")
      (node (ref "U315") (pin "42") (pinfunction "PE6/SYNC/RXD1/MISO/TOSC2_42") (pintype "bidirectional+no_connect"))
    )
    (net (code "113") (name "unconnected-(U315A-PE7{slash}SYNC{slash}TXD1{slash}SCK{slash}CLKOUT{slash}EVOUT{slash}TOSC1-Pad43)") (class "Default")
      (node (ref "U315") (pin "43") (pinfunction "PE7/SYNC/TXD1/SCK/CLKOUT/EVOUT/TOSC1_43") (pintype "bidirectional+no_connect"))
    )
    (net (code "114") (name "unconnected-(U315A-PF7{slash}SYNC-Pad55)") (class "Default")
      (node (ref "U315") (pin "55") (pinfunction "PF7/SYNC_55") (pintype "bidirectional+no_connect"))
    )
    (net (code "115") (name "unconnected-(U317C-Y-Pad10)") (class "Default")
      (node (ref "U317") (pin "10") (pinfunction "Y_10") (pintype "output+no_connect"))
    )
    (net (code "116") (name "unconnected-(U317D-Y-Pad13)") (class "Default")
      (node (ref "U317") (pin "13") (pinfunction "Y_13") (pintype "output+no_connect"))
    )
  )
)
